# 06_MCU.net
KiCad netlist of a schematic drawn in Altium Designer
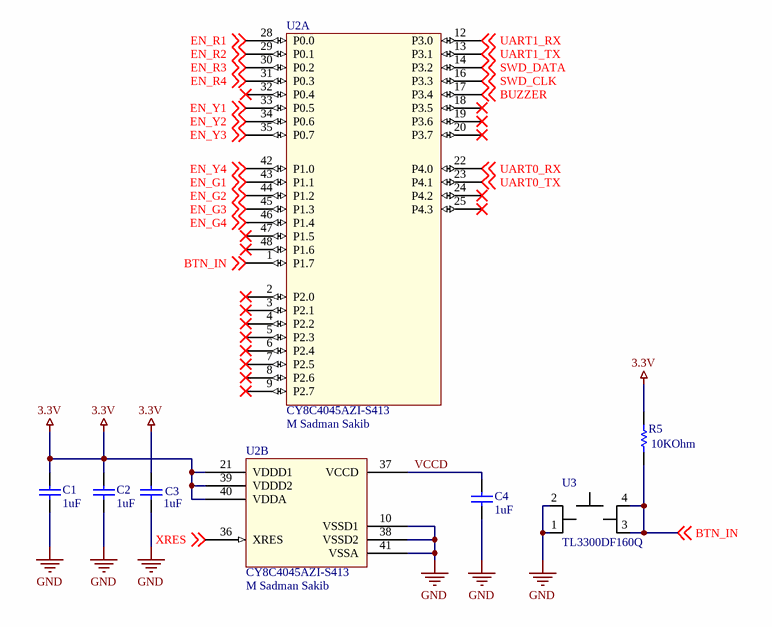
[diagram p0: 06_MCU.SchDoc]

(export (version "E")
  (design (tool "Eeschema 10.0.6"))
  (components
    (comp (ref "C1")
      (value "C1206C105K3RACTU")
      (footprint "CAPC3216X180X50ML20T25")
      (description "Chip Capacitor, 1 uF, +/- 10%, 25 V, -55 to 125 degC, 1206 (3216 Metric), RoHS, Tape and Reel")
      (fields
        (field (name "CAPACITANCE") "1uF")
        (field (name "MANUFACTURER") "Kemet")
        (field (name "TOLERANCE") "10%")
      )
      (libsource (lib "Altium Content Vault") (part "CAP-NP-2"))
    )
    (comp (ref "C2")
      (value "C1206C105K3RACTU")
      (footprint "CAPC3216X180X50ML20T25")
      (description "Chip Capacitor, 1 uF, +/- 10%, 25 V, -55 to 125 degC, 1206 (3216 Metric), RoHS, Tape and Reel")
      (fields
        (field (name "CAPACITANCE") "1uF")
        (field (name "MANUFACTURER") "Kemet")
        (field (name "TOLERANCE") "10%")
      )
      (libsource (lib "Altium Content Vault") (part "CAP-NP-2"))
    )
    (comp (ref "C3")
      (value "C1206C105K3RACTU")
      (footprint "CAPC3216X180X50ML20T25")
      (description "Chip Capacitor, 1 uF, +/- 10%, 25 V, -55 to 125 degC, 1206 (3216 Metric), RoHS, Tape and Reel")
      (fields
        (field (name "CAPACITANCE") "1uF")
        (field (name "MANUFACTURER") "Kemet")
        (field (name "TOLERANCE") "10%")
      )
      (libsource (lib "Altium Content Vault") (part "CAP-NP-2"))
    )
    (comp (ref "C4")
      (value "C1206C105K3RACTU")
      (footprint "CAPC3216X180X50ML20T25")
      (description "Chip Capacitor, 1 uF, +/- 10%, 25 V, -55 to 125 degC, 1206 (3216 Metric), RoHS, Tape and Reel")
      (fields
        (field (name "CAPACITANCE") "1uF")
        (field (name "MANUFACTURER") "Kemet")
        (field (name "TOLERANCE") "10%")
      )
      (libsource (lib "Altium Content Vault") (part "CAP-NP-2"))
    )
    (comp (ref "R5")
      (value "RC1206FR-0710KL")
      (footprint "RESC3116X65X40ML10T20")
      (description "Chip Resistor, 10 KOhm, +/- 1%, 0.25 W, -55 to 155 degC, 1206 (3216 Metric), RoHS, Tape and Reel")
      (fields
        (field (name "TOLERANCE") "1%")
        (field (name "RESISTANCE") "10KOhm")
        (field (name "MANUFACTURER") "Yageo")
      )
      (libsource (lib "Altium Content Vault") (part "RES-2"))
    )
    (comp (ref "U2")
      (value "CY8C4045AZI-S413")
      (footprint "TQFP48_7X7")
      (description "ARM Microcontrollers - MCU PSoC4")
      (fields (field (name "M SADMAN SAKIB") "M Sadman Sakib"))
      (libsource (lib "ECE315") (part "CY8C4045AZI-S413"))
    )
    (comp (ref "U3")
      (value "TL3300DF160Q")
      (footprint "TL3300DF160Q")
      (description "Switch Tactile OFF (ON) SPST Round Button Gull Wing 0.05A 12VDC 1.57N SMD")
      (fields (field (name "MANUFACTURER") "E-Switch"))
      (libsource (lib "ECE315") (part "TL3300DF160Q"))
    )
  )
  (nets
    (net (code "1") (name "/VCCD") (class "Default")
      (node (ref "C4") (pin "2") (pinfunction "2_2") (pintype "passive"))
      (node (ref "U2") (pin "37") (pinfunction "VCCD_37") (pintype "power_in"))
    )
    (net (code "2") (name "3.3V") (class "Default")
      (node (ref "C1") (pin "2") (pinfunction "2_2") (pintype "passive"))
      (node (ref "C2") (pin "2") (pinfunction "2_2") (pintype "passive"))
      (node (ref "C3") (pin "2") (pinfunction "2_2") (pintype "passive"))
      (node (ref "R5") (pin "2") (pinfunction "2_2") (pintype "passive"))
      (node (ref "U2") (pin "21") (pinfunction "VDDD1_21") (pintype "power_in"))
      (node (ref "U2") (pin "39") (pinfunction "VDDD2_39") (pintype "power_in"))
      (node (ref "U2") (pin "40") (pinfunction "VDDA_40") (pintype "power_in"))
    )
    (net (code "3") (name "BTN_IN") (class "Default")
      (node (ref "R5") (pin "1") (pinfunction "1_1") (pintype "passive"))
      (node (ref "U2") (pin "1") (pinfunction "P1.7_1") (pintype "bidirectional"))
      (node (ref "U3") (pin "3") (pinfunction "3_3") (pintype "passive"))
      (node (ref "U3") (pin "4") (pinfunction "VCCIO_4") (pintype "passive"))
    )
    (net (code "4") (name "BUZZER") (class "Default")
      (node (ref "U2") (pin "17") (pinfunction "P3.4_17") (pintype "bidirectional"))
    )
    (net (code "5") (name "EN_G1") (class "Default")
      (node (ref "U2") (pin "43") (pinfunction "P1.1_43") (pintype "bidirectional"))
    )
    (net (code "6") (name "EN_G2") (class "Default")
      (node (ref "U2") (pin "44") (pinfunction "P1.2_44") (pintype "bidirectional"))
    )
    (net (code "7") (name "EN_G3") (class "Default")
      (node (ref "U2") (pin "45") (pinfunction "P1.3_45") (pintype "bidirectional"))
    )
    (net (code "8") (name "EN_G4") (class "Default")
      (node (ref "U2") (pin "46") (pinfunction "P1.4_46") (pintype "bidirectional"))
    )
    (net (code "9") (name "EN_R1") (class "Default")
      (node (ref "U2") (pin "28") (pinfunction "P0.0_28") (pintype "bidirectional"))
    )
    (net (code "10") (name "EN_R2") (class "Default")
      (node (ref "U2") (pin "29") (pinfunction "P0.1_29") (pintype "bidirectional"))
    )
    (net (code "11") (name "EN_R3") (class "Default")
      (node (ref "U2") (pin "30") (pinfunction "P0.2_30") (pintype "bidirectional"))
    )
    (net (code "12") (name "EN_R4") (class "Default")
      (node (ref "U2") (pin "31") (pinfunction "P0.3_31") (pintype "bidirectional"))
    )
    (net (code "13") (name "EN_Y1") (class "Default")
      (node (ref "U2") (pin "33") (pinfunction "P0.5_33") (pintype "bidirectional"))
    )
    (net (code "14") (name "EN_Y2") (class "Default")
      (node (ref "U2") (pin "34") (pinfunction "P0.6_34") (pintype "bidirectional"))
    )
    (net (code "15") (name "EN_Y3") (class "Default")
      (node (ref "U2") (pin "35") (pinfunction "P0.7_35") (pintype "bidirectional"))
    )
    (net (code "16") (name "EN_Y4") (class "Default")
      (node (ref "U2") (pin "42") (pinfunction "P1.0_42") (pintype "bidirectional"))
    )
    (net (code "17") (name "GND") (class "Default")
      (node (ref "C1") (pin "1") (pinfunction "1_1") (pintype "passive"))
      (node (ref "C2") (pin "1") (pinfunction "1_1") (pintype "passive"))
      (node (ref "C3") (pin "1") (pinfunction "1_1") (pintype "passive"))
      (node (ref "C4") (pin "1") (pinfunction "1_1") (pintype "passive"))
      (node (ref "U2") (pin "10") (pinfunction "VSSD1_10") (pintype "power_in"))
      (node (ref "U2") (pin "38") (pinfunction "VSSD2_38") (pintype "power_in"))
      (node (ref "U2") (pin "41") (pinfunction "VSSA_41") (pintype "power_in"))
      (node (ref "U3") (pin "1") (pinfunction "1_1") (pintype "passive"))
      (node (ref "U3") (pin "2") (pinfunction "2_2") (pintype "passive"))
    )
    (net (code "18") (name "SWD_CLK") (class "Default")
      (node (ref "U2") (pin "16") (pinfunction "P3.3_16") (pintype "bidirectional"))
    )
    (net (code "19") (name "SWD_DATA") (class "Default")
      (node (ref "U2") (pin "14") (pinfunction "P3.2_14") (pintype "bidirectional"))
    )
    (net (code "20") (name "UART0_RX") (class "Default")
      (node (ref "U2") (pin "22") (pinfunction "P4.0_22") (pintype "bidirectional"))
    )
    (net (code "21") (name "UART0_TX") (class "Default")
      (node (ref "U2") (pin "23") (pinfunction "P4.1_23") (pintype "bidirectional"))
    )
    (net (code "22") (name "UART1_RX") (class "Default")
      (node (ref "U2") (pin "12") (pinfunction "P3.0_12") (pintype "bidirectional"))
    )
    (net (code "23") (name "UART1_TX") (class "Default")
      (node (ref "U2") (pin "13") (pinfunction "P3.1_13") (pintype "bidirectional"))
    )
    (net (code "24") (name "XRES") (class "Default")
      (node (ref "U2") (pin "36") (pinfunction "XRES_36") (pintype "input"))
    )
    (net (code "25") (name "unconnected-(U2A-P0.4-Pad32)") (class "Default")
      (node (ref "U2") (pin "32") (pinfunction "P0.4_32") (pintype "bidirectional+no_connect"))
    )
    (net (code "26") (name "unconnected-(U2A-P1.5-Pad47)") (class "Default")
      (node (ref "U2") (pin "47") (pinfunction "P1.5_47") (pintype "bidirectional+no_connect"))
    )
    (net (code "27") (name "unconnected-(U2A-P1.6-Pad48)") (class "Default")
      (node (ref "U2") (pin "48") (pinfunction "P1.6_48") (pintype "bidirectional+no_connect"))
    )
    (net (code "28") (name "unconnected-(U2A-P2.0-Pad2)") (class "Default")
      (node (ref "U2") (pin "2") (pinfunction "P2.0_2") (pintype "bidirectional+no_connect"))
    )
    (net (code "29") (name "unconnected-(U2A-P2.1-Pad3)") (class "Default")
      (node (ref "U2") (pin "3") (pinfunction "P2.1_3") (pintype "bidirectional+no_connect"))
    )
    (net (code "30") (name "unconnected-(U2A-P2.2-Pad4)") (class "Default")
      (node (ref "U2") (pin "4") (pinfunction "P2.2_4") (pintype "bidirectional+no_connect"))
    )
    (net (code "31") (name "unconnected-(U2A-P2.3-Pad5)") (class "Default")
      (node (ref "U2") (pin "5") (pinfunction "P2.3_5") (pintype "bidirectional+no_connect"))
    )
    (net (code "32") (name "unconnected-(U2A-P2.4-Pad6)") (class "Default")
      (node (ref "U2") (pin "6") (pinfunction "P2.4_6") (pintype "bidirectional+no_connect"))
    )
    (net (code "33") (name "unconnected-(U2A-P2.5-Pad7)") (class "Default")
      (node (ref "U2") (pin "7") (pinfunction "P2.5_7") (pintype "bidirectional+no_connect"))
    )
    (net (code "34") (name "unconnected-(U2A-P2.6-Pad8)") (class "Default")
      (node (ref "U2") (pin "8") (pinfunction "P2.6_8") (pintype "bidirectional+no_connect"))
    )
    (net (code "35") (name "unconnected-(U2A-P2.7-Pad9)") (class "Default")
      (node (ref "U2") (pin "9") (pinfunction "P2.7_9") (pintype "bidirectional+no_connect"))
    )
    (net (code "36") (name "unconnected-(U2A-P3.5-Pad18)") (class "Default")
      (node (ref "U2") (pin "18") (pinfunction "P3.5_18") (pintype "bidirectional+no_connect"))
    )
    (net (code "37") (name "unconnected-(U2A-P3.6-Pad19)") (class "Default")
      (node (ref "U2") (pin "19") (pinfunction "P3.6_19") (pintype "bidirectional+no_connect"))
    )
    (net (code "38") (name "unconnected-(U2A-P3.7-Pad20)") (class "Default")
      (node (ref "U2") (pin "20") (pinfunction "P3.7_20") (pintype "bidirectional+no_connect"))
    )
    (net (code "39") (name "unconnected-(U2A-P4.2-Pad24)") (class "Default")
      (node (ref "U2") (pin "24") (pinfunction "P4.2_24") (pintype "bidirectional+no_connect"))
    )
    (net (code "40") (name "unconnected-(U2A-P4.3-Pad25)") (class "Default")
      (node (ref "U2") (pin "25") (pinfunction "P4.3_25") (pintype "bidirectional+no_connect"))
    )
  )
)
